# Smart_Smoke_Detector.net
KiCad netlist of a schematic drawn in Altium Designer
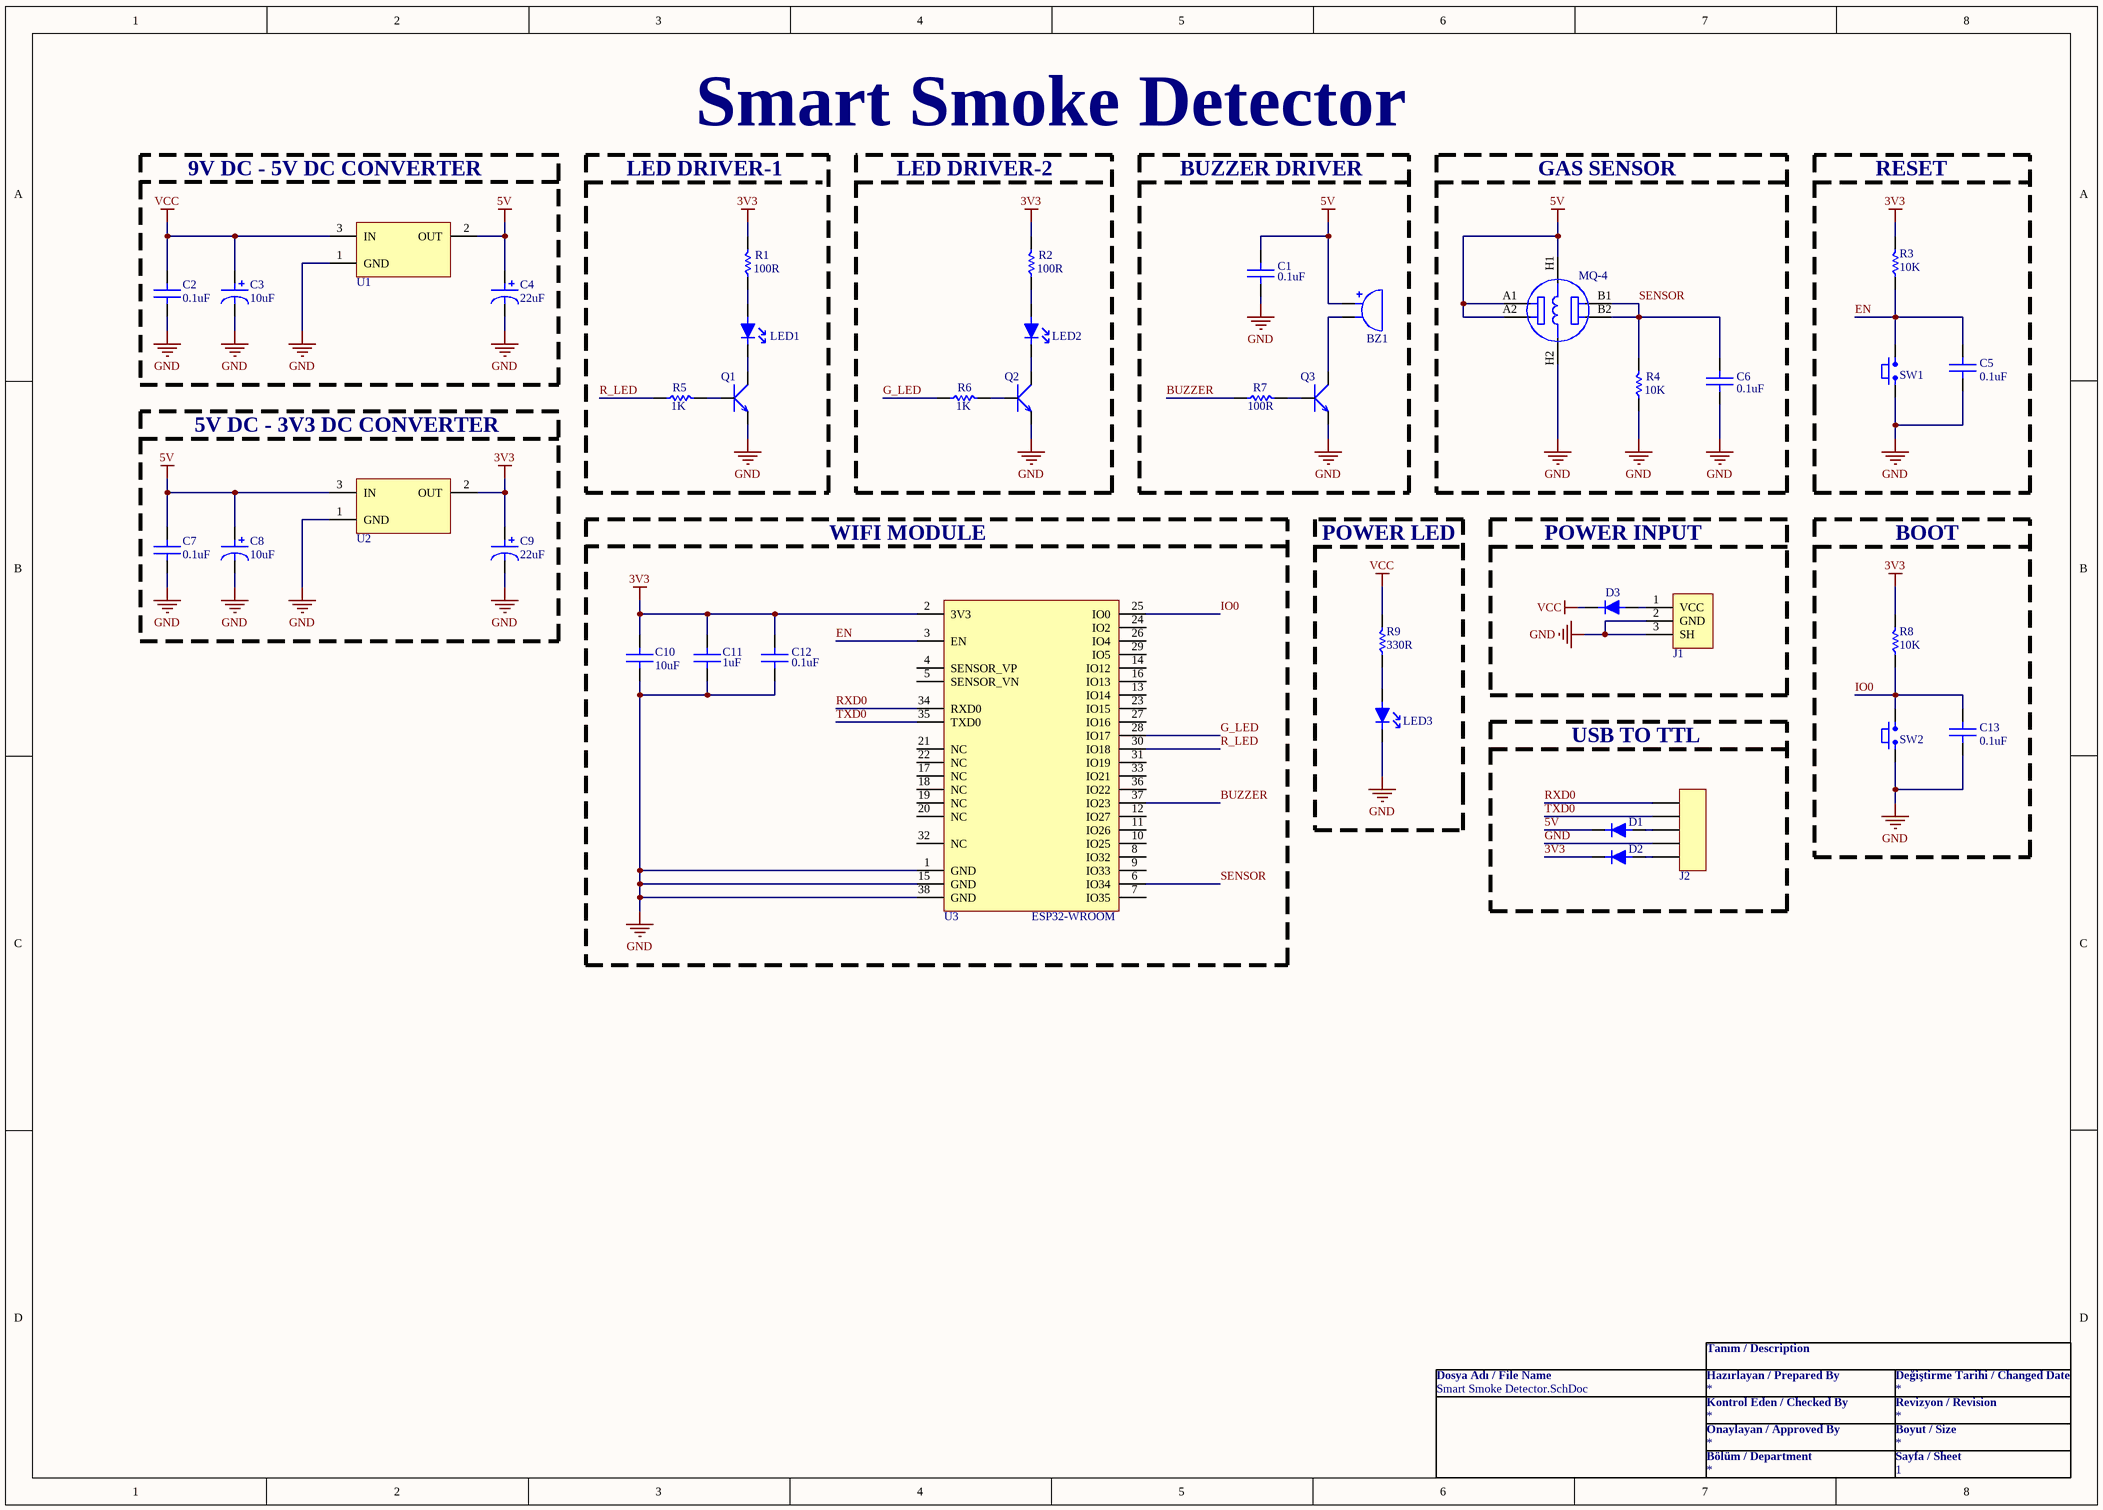
[diagram p0: Smart Smoke Detector.SchDoc]

(export (version "E")
  (design (tool "Eeschema 10.0.6"))
  (components
    (comp (ref "BZ1")
      (value "AI-1223-TWT-3V-2-R")
      (footprint "BUZZER")
      (description "BUZZER MAGNETIC 3V 12MM TH")
      (libsource (lib "Smart Smoke Detector") (part "BUZZER TH"))
    )
    (comp (ref "C1")
      (value "0.1uF")
      (footprint "CAP 0805")
      (description "CAP CER 0.1UF 50V X7R 0805")
      (fields (field (name "Comment") "CC0805KRX7R9BB104"))
      (libsource (lib "Smart Smoke Detector") (part "CAP CER 0.1UF 0805 SMD"))
    )
    (comp (ref "C2")
      (value "0.1uF")
      (footprint "CAP 0805")
      (description "CAP CER 0.1UF 50V X7R 0805")
      (fields (field (name "Comment") "CC0805KRX7R9BB104"))
      (libsource (lib "Smart Smoke Detector") (part "CAP CER 0.1UF 0805 SMD"))
    )
    (comp (ref "C3")
      (value "10uF")
      (footprint "CAP ALUM 10UF")
      (description "CAP ALUM 10UF 20% 16V SMD")
      (fields (field (name "Comment") "875105359001"))
      (libsource (lib "Smart Smoke Detector") (part "CAP ALUM 10UF SMD"))
    )
    (comp (ref "C4")
      (value "22uF")
      (footprint "CAP ALUM 22UF")
      (description "CAP ALUM 22UF 20% 20V SMD")
      (fields (field (name "Comment") "A766EB226M1DLAE060"))
      (libsource (lib "Smart Smoke Detector") (part "CAP ALUM 22UF SMD"))
    )
    (comp (ref "C5")
      (value "0.1uF")
      (footprint "CAP 0805")
      (description "CAP CER 0.1UF 50V X7R 0805")
      (fields (field (name "Comment") "CC0805KRX7R9BB104"))
      (libsource (lib "Smart Smoke Detector") (part "CAP CER 0.1UF 0805 SMD"))
    )
    (comp (ref "C6")
      (value "0.1uF")
      (footprint "CAP 0805")
      (description "CAP CER 0.1UF 50V X7R 0805")
      (fields (field (name "Comment") "CC0805KRX7R9BB104"))
      (libsource (lib "Smart Smoke Detector") (part "CAP CER 0.1UF 0805 SMD"))
    )
    (comp (ref "C7")
      (value "0.1uF")
      (footprint "CAP 0805")
      (description "CAP CER 0.1UF 50V X7R 0805")
      (fields (field (name "Comment") "CC0805KRX7R9BB104"))
      (libsource (lib "Smart Smoke Detector") (part "CAP CER 0.1UF 0805 SMD"))
    )
    (comp (ref "C8")
      (value "10uF")
      (footprint "CAP ALUM 10UF")
      (description "CAP ALUM 10UF 20% 16V SMD")
      (fields (field (name "Comment") "875105359001"))
      (libsource (lib "Smart Smoke Detector") (part "CAP ALUM 10UF SMD"))
    )
    (comp (ref "C9")
      (value "22uF")
      (footprint "CAP ALUM 22UF")
      (description "CAP ALUM 22UF 20% 20V SMD")
      (fields (field (name "Comment") "A766EB226M1DLAE060"))
      (libsource (lib "Smart Smoke Detector") (part "CAP ALUM 22UF SMD"))
    )
    (comp (ref "C10")
      (value "10uF")
      (footprint "CAP 0805")
      (description "CAP CER 10UF 25V X5R 0805")
      (fields (field (name "Comment") "CC0805KKX5R8BB106"))
      (libsource (lib "Smart Smoke Detector") (part "CAP CER 10UF 0805 SMD"))
    )
    (comp (ref "C11")
      (value "1uF")
      (footprint "CAP 0805")
      (description "CAP CER 1UF 50V X7R 0805")
      (fields (field (name "Comment") "CC0805KKX7R9BB105"))
      (libsource (lib "Smart Smoke Detector") (part "CAP CER 1UF 0805 SMD"))
    )
    (comp (ref "C12")
      (value "0.1uF")
      (footprint "CAP 0805")
      (description "CAP CER 0.1UF 50V X7R 0805")
      (fields (field (name "Comment") "CC0805KRX7R9BB104"))
      (libsource (lib "Smart Smoke Detector") (part "CAP CER 0.1UF 0805 SMD"))
    )
    (comp (ref "C13")
      (value "0.1uF")
      (footprint "CAP 0805")
      (description "CAP CER 0.1UF 50V X7R 0805")
      (fields (field (name "Comment") "CC0805KRX7R9BB104"))
      (libsource (lib "Smart Smoke Detector") (part "CAP CER 0.1UF 0805 SMD"))
    )
    (comp (ref "D1")
      (value "1N5819W")
      (footprint "SOD-123F")
      (description "DIODE SCHOTTKY 40V 1A SOD-123F")
      (libsource (lib "Smart Smoke Detector") (part "SCHOTTKY DIODE SMD"))
    )
    (comp (ref "D2")
      (value "1N5819W")
      (footprint "SOD-123F")
      (description "DIODE SCHOTTKY 40V 1A SOD-123F")
      (libsource (lib "Smart Smoke Detector") (part "SCHOTTKY DIODE SMD"))
    )
    (comp (ref "D3")
      (value "1N5819W")
      (footprint "SOD-123F")
      (description "DIODE SCHOTTKY 40V 1A SOD-123F")
      (libsource (lib "Smart Smoke Detector") (part "SCHOTTKY DIODE SMD"))
    )
    (comp (ref "GAS1")
      (value "MQ-4")
      (footprint "MQ-4")
      (description "SENSOR METHANE 2.5V-4 V OUTPUT")
      (fields (field (name "Comment") "SEN-09404"))
      (libsource (lib "Smart Smoke Detector") (part "MQ-4 SENSOR"))
    )
    (comp (ref "J1")
      (value "PJ-036BH-SMT-TR")
      (footprint "POWER JACK")
      (description "PWR JACK 2.5X5.5MM SOLDER")
      (libsource (lib "Smart Smoke Detector") (part "POWER JACK SMD"))
    )
    (comp (ref "J2")
      (value "SMH-105-02-L-S")
      (footprint "SMD HEADER")
      (description "FEMALE HEADER 5POS 2.54MM")
      (libsource (lib "Smart Smoke Detector") (part "HEADER 5POS SMD"))
    )
    (comp (ref "LED1")
      (value "151031SS06000")
      (footprint "RED LED")
      (description "LED RED 3MM ROUND T/H")
      (libsource (lib "Smart Smoke Detector") (part "LED RED TH"))
    )
    (comp (ref "LED2")
      (value "151031VS06000")
      (footprint "GREEN LED")
      (description "LED GREEN 3MM ROUND T/H")
      (libsource (lib "Smart Smoke Detector") (part "LED GREEN TH"))
    )
    (comp (ref "LED3")
      (value "151031VS06000")
      (footprint "GREEN LED")
      (description "LED GREEN 3MM ROUND T/H")
      (libsource (lib "Smart Smoke Detector") (part "LED GREEN TH"))
    )
    (comp (ref "Q1")
      (value "MMBT3904-7-F")
      (footprint "SOT-23-3")
      (description "TRANS NPN 40V 0.2A SOT23-3")
      (libsource (lib "Smart Smoke Detector") (part "NPN TRANSISTOR SMD"))
    )
    (comp (ref "Q2")
      (value "MMBT3904-7-F")
      (footprint "SOT-23-3")
      (description "TRANS NPN 40V 0.2A SOT23-3")
      (libsource (lib "Smart Smoke Detector") (part "NPN TRANSISTOR SMD"))
    )
    (comp (ref "Q3")
      (value "MMBT3904-7-F")
      (footprint "SOT-23-3")
      (description "TRANS NPN 40V 0.2A SOT23-3")
      (libsource (lib "Smart Smoke Detector") (part "NPN TRANSISTOR SMD"))
    )
    (comp (ref "R1")
      (value "100R")
      (footprint "RES 0805")
      (description "RES 100 OHM 1% 1/8W 0805")
      (fields (field (name "Comment") "RMCF0805FT100R"))
      (libsource (lib "Smart Smoke Detector") (part "RES 100 OHM 0805 SMD"))
    )
    (comp (ref "R2")
      (value "100R")
      (footprint "RES 0805")
      (description "RES 100 OHM 1% 1/8W 0805")
      (fields (field (name "Comment") "RMCF0805FT100R"))
      (libsource (lib "Smart Smoke Detector") (part "RES 100 OHM 0805 SMD"))
    )
    (comp (ref "R3")
      (value "10K")
      (footprint "RES 0805")
      (description "RES 10K OHM 5% 1/8W 0805")
      (fields (field (name "Comment") "ERJ-6GEYJ103V"))
      (libsource (lib "Smart Smoke Detector") (part "RES 10K OHM 0805 SMD"))
    )
    (comp (ref "R4")
      (value "10K")
      (footprint "RES 0805")
      (description "RES SMD 10K OHM 5% 1/8W 0805")
      (fields (field (name "Comment") "ERJ-6GEYJ103V"))
      (libsource (lib "Smart Smoke Detector") (part "RES 10K OHM 0805 SMD"))
    )
    (comp (ref "R5")
      (value "1K")
      (footprint "RES 0805")
      (description "RES 1K OHM 1% 1/8W 0805")
      (fields (field (name "Comment") "RC0805FR-071KL"))
      (libsource (lib "Smart Smoke Detector") (part "RES 1K OHM 0805 SMD"))
    )
    (comp (ref "R6")
      (value "1K")
      (footprint "RES 0805")
      (description "RES 1K OHM 1% 1/8W 0805")
      (fields (field (name "Comment") "RC0805FR-071KL"))
      (libsource (lib "Smart Smoke Detector") (part "RES 1K OHM 0805 SMD"))
    )
    (comp (ref "R7")
      (value "100R")
      (footprint "RES 0805")
      (description "RES 100 OHM 1% 1/8W 0805")
      (fields (field (name "Comment") "RMCF0805FT100R"))
      (libsource (lib "Smart Smoke Detector") (part "RES 100 OHM 0805 SMD"))
    )
    (comp (ref "R8")
      (value "10K")
      (footprint "RES 0805")
      (description "RES 10K OHM 5% 1/8W 0805")
      (fields (field (name "Comment") "ERJ-6GEYJ103V"))
      (libsource (lib "Smart Smoke Detector") (part "RES 10K OHM 0805 SMD"))
    )
    (comp (ref "R9")
      (value "330R")
      (footprint "RES 0805")
      (description "RES 330 OHM 1% 1/8W 0805")
      (fields (field (name "Comment") "RC0805FR-07330RL"))
      (libsource (lib "Smart Smoke Detector") (part "RES 330 OHM 0805 SMD"))
    )
    (comp (ref "SW1")
      (value "PTS636 SK25F SMTR LFS")
      (footprint "TACTILE SWITCH")
      (description "SWITCH TACTILE 0.05A 12V")
      (libsource (lib "Smart Smoke Detector") (part "TACTILE SWITCH SMD"))
    )
    (comp (ref "SW2")
      (value "PTS636 SK25F SMTR LFS")
      (footprint "TACTILE SWITCH")
      (description "SWITCH TACTILE 0.05A 12V")
      (libsource (lib "Smart Smoke Detector") (part "TACTILE SWITCH SMD"))
    )
    (comp (ref "U1")
      (value "AMS1117-5.0")
      (footprint "SOT-223")
      (description "IC LDO REG 5V 1A SOT223")
      (libsource (lib "Smart Smoke Detector") (part "LDO REG 5V 1A SMD"))
    )
    (comp (ref "U2")
      (value "AMS1117-3.3")
      (footprint "SOT-223")
      (description "IC LDO REG 3.3V 1A SOT223")
      (libsource (lib "Smart Smoke Detector") (part "LDO REG 3V3 1A SMD"))
    )
    (comp (ref "U3")
      (value "ESP32-WROOM")
      (footprint "ESP32")
      (description "RF TXRX MOD BT WIFI TH SMD")
      (fields (field (name "Comment") "ESP32-WROOM-32E-H4"))
      (libsource (lib "Smart Smoke Detector") (part "ESP32-WROOM-32E"))
    )
  )
  (nets
    (net (code "1") (name "/BUZZER") (class "Default")
      (node (ref "R7") (pin "1") (pinfunction "1_1") (pintype "passive"))
      (node (ref "U3") (pin "37") (pinfunction "IO23_37") (pintype "passive"))
    )
    (net (code "2") (name "/EN") (class "Default")
      (node (ref "C5") (pin "2") (pintype "passive"))
      (node (ref "R3") (pin "1") (pinfunction "1_1") (pintype "passive"))
      (node (ref "SW1") (pin "2") (pintype "passive"))
      (node (ref "U3") (pin "3") (pinfunction "EN_3") (pintype "passive"))
    )
    (net (code "3") (name "/G_LED") (class "Default")
      (node (ref "R6") (pin "1") (pinfunction "1_1") (pintype "passive"))
      (node (ref "U3") (pin "28") (pinfunction "IO17_28") (pintype "passive"))
    )
    (net (code "4") (name "/IO0") (class "Default")
      (node (ref "C13") (pin "2") (pintype "passive"))
      (node (ref "R8") (pin "1") (pinfunction "1_1") (pintype "passive"))
      (node (ref "SW2") (pin "2") (pintype "passive"))
      (node (ref "U3") (pin "25") (pinfunction "IO0_25") (pintype "passive"))
    )
    (net (code "5") (name "/RXD0") (class "Default")
      (node (ref "J2") (pin "1") (pintype "passive"))
      (node (ref "U3") (pin "34") (pinfunction "RXD0_34") (pintype "passive"))
    )
    (net (code "6") (name "/R_LED") (class "Default")
      (node (ref "R5") (pin "1") (pinfunction "1_1") (pintype "passive"))
      (node (ref "U3") (pin "30") (pinfunction "IO18_30") (pintype "passive"))
    )
    (net (code "7") (name "/SENSOR") (class "Default")
      (node (ref "C6") (pin "2") (pintype "passive"))
      (node (ref "GAS1") (pin "B1") (pintype "passive"))
      (node (ref "GAS1") (pin "B2") (pintype "passive"))
      (node (ref "R4") (pin "2") (pinfunction "2_2") (pintype "passive"))
      (node (ref "U3") (pin "6") (pinfunction "IO34_6") (pintype "passive"))
    )
    (net (code "8") (name "/TXD0") (class "Default")
      (node (ref "J2") (pin "2") (pintype "passive"))
      (node (ref "U3") (pin "35") (pinfunction "TXD0_35") (pintype "passive"))
    )
    (net (code "9") (name "3V3") (class "Default")
      (node (ref "C10") (pin "2") (pintype "passive"))
      (node (ref "C11") (pin "1") (pintype "passive"))
      (node (ref "C12") (pin "1") (pintype "passive"))
      (node (ref "C9") (pin "1") (pintype "passive"))
      (node (ref "D2") (pin "2") (pintype "passive"))
      (node (ref "R1") (pin "2") (pinfunction "2_2") (pintype "passive"))
      (node (ref "R2") (pin "2") (pinfunction "2_2") (pintype "passive"))
      (node (ref "R3") (pin "2") (pinfunction "2_2") (pintype "passive"))
      (node (ref "R8") (pin "2") (pinfunction "2_2") (pintype "passive"))
      (node (ref "U2") (pin "2") (pinfunction "OUT_2") (pintype "passive"))
      (node (ref "U3") (pin "2") (pinfunction "3V3_2") (pintype "passive"))
    )
    (net (code "10") (name "5V") (class "Default")
      (node (ref "BZ1") (pin "1") (pintype "passive"))
      (node (ref "C1") (pin "2") (pintype "passive"))
      (node (ref "C4") (pin "1") (pintype "passive"))
      (node (ref "C7") (pin "2") (pintype "passive"))
      (node (ref "C8") (pin "1") (pintype "passive"))
      (node (ref "D1") (pin "2") (pintype "passive"))
      (node (ref "GAS1") (pin "A1") (pintype "passive"))
      (node (ref "GAS1") (pin "A2") (pintype "passive"))
      (node (ref "GAS1") (pin "H1") (pintype "passive"))
      (node (ref "U1") (pin "2") (pinfunction "OUT_2") (pintype "passive"))
      (node (ref "U2") (pin "3") (pinfunction "IN_3") (pintype "passive"))
    )
    (net (code "11") (name "GND") (class "Default")
      (node (ref "C1") (pin "1") (pintype "passive"))
      (node (ref "C10") (pin "1") (pintype "passive"))
      (node (ref "C11") (pin "2") (pintype "passive"))
      (node (ref "C12") (pin "2") (pintype "passive"))
      (node (ref "C13") (pin "1") (pintype "passive"))
      (node (ref "C2") (pin "1") (pintype "passive"))
      (node (ref "C3") (pin "2") (pintype "passive"))
      (node (ref "C4") (pin "2") (pintype "passive"))
      (node (ref "C5") (pin "1") (pintype "passive"))
      (node (ref "C6") (pin "1") (pintype "passive"))
      (node (ref "C7") (pin "1") (pintype "passive"))
      (node (ref "C8") (pin "2") (pintype "passive"))
      (node (ref "C9") (pin "2") (pintype "passive"))
      (node (ref "GAS1") (pin "H2") (pintype "passive"))
      (node (ref "J1") (pin "2") (pinfunction "GND_2") (pintype "passive"))
      (node (ref "J1") (pin "3") (pinfunction "SH_3") (pintype "passive"))
      (node (ref "J2") (pin "4") (pintype "passive"))
      (node (ref "LED3") (pin "2") (pintype "passive"))
      (node (ref "Q1") (pin "2") (pintype "passive"))
      (node (ref "Q2") (pin "2") (pintype "passive"))
      (node (ref "Q3") (pin "2") (pintype "passive"))
      (node (ref "R4") (pin "1") (pinfunction "1_1") (pintype "passive"))
      (node (ref "SW1") (pin "1") (pintype "passive"))
      (node (ref "SW2") (pin "1") (pintype "passive"))
      (node (ref "U1") (pin "1") (pinfunction "GND_1") (pintype "passive"))
      (node (ref "U2") (pin "1") (pinfunction "GND_1") (pintype "passive"))
      (node (ref "U3") (pin "1") (pinfunction "GND_1") (pintype "passive"))
      (node (ref "U3") (pin "15") (pinfunction "GND_15") (pintype "passive"))
      (node (ref "U3") (pin "38") (pinfunction "GND_38") (pintype "passive"))
    )
    (net (code "12") (name "Net-(BZ1-Pad2)") (class "Default")
      (node (ref "BZ1") (pin "2") (pintype "passive"))
      (node (ref "Q3") (pin "3") (pintype "passive"))
    )
    (net (code "13") (name "Net-(D1-Pad1)") (class "Default")
      (node (ref "D1") (pin "1") (pintype "passive"))
      (node (ref "J2") (pin "3") (pintype "passive"))
    )
    (net (code "14") (name "Net-(D2-Pad1)") (class "Default")
      (node (ref "D2") (pin "1") (pintype "passive"))
      (node (ref "J2") (pin "5") (pintype "passive"))
    )
    (net (code "15") (name "Net-(J1-VCC)") (class "Default")
      (node (ref "D3") (pin "1") (pintype "passive"))
      (node (ref "J1") (pin "1") (pinfunction "VCC_1") (pintype "passive"))
    )
    (net (code "16") (name "Net-(LED1-Pad1)") (class "Default")
      (node (ref "LED1") (pin "1") (pintype "passive"))
      (node (ref "R1") (pin "1") (pinfunction "1_1") (pintype "passive"))
    )
    (net (code "17") (name "Net-(LED1-Pad2)") (class "Default")
      (node (ref "LED1") (pin "2") (pintype "passive"))
      (node (ref "Q1") (pin "3") (pintype "passive"))
    )
    (net (code "18") (name "Net-(LED2-Pad1)") (class "Default")
      (node (ref "LED2") (pin "1") (pintype "passive"))
      (node (ref "R2") (pin "1") (pinfunction "1_1") (pintype "passive"))
    )
    (net (code "19") (name "Net-(LED2-Pad2)") (class "Default")
      (node (ref "LED2") (pin "2") (pintype "passive"))
      (node (ref "Q2") (pin "3") (pintype "passive"))
    )
    (net (code "20") (name "Net-(LED3-Pad1)") (class "Default")
      (node (ref "LED3") (pin "1") (pintype "passive"))
      (node (ref "R9") (pin "1") (pinfunction "1_1") (pintype "passive"))
    )
    (net (code "21") (name "Net-(Q1-Pad1)") (class "Default")
      (node (ref "Q1") (pin "1") (pintype "passive"))
      (node (ref "R5") (pin "2") (pinfunction "2_2") (pintype "passive"))
    )
    (net (code "22") (name "Net-(Q2-Pad1)") (class "Default")
      (node (ref "Q2") (pin "1") (pintype "passive"))
      (node (ref "R6") (pin "2") (pinfunction "2_2") (pintype "passive"))
    )
    (net (code "23") (name "Net-(Q3-Pad1)") (class "Default")
      (node (ref "Q3") (pin "1") (pintype "passive"))
      (node (ref "R7") (pin "2") (pinfunction "2_2") (pintype "passive"))
    )
    (net (code "24") (name "VCC") (class "Default")
      (node (ref "C2") (pin "2") (pintype "passive"))
      (node (ref "C3") (pin "1") (pintype "passive"))
      (node (ref "D3") (pin "2") (pintype "passive"))
      (node (ref "R9") (pin "2") (pinfunction "2_2") (pintype "passive"))
      (node (ref "U1") (pin "3") (pinfunction "IN_3") (pintype "passive"))
    )
    (net (code "25") (name "unconnected-(U3-IO2-Pad24)") (class "Default")
      (node (ref "U3") (pin "24") (pinfunction "IO2_24") (pintype "passive"))
    )
    (net (code "26") (name "unconnected-(U3-IO4-Pad26)") (class "Default")
      (node (ref "U3") (pin "26") (pinfunction "IO4_26") (pintype "passive"))
    )
    (net (code "27") (name "unconnected-(U3-IO5-Pad29)") (class "Default")
      (node (ref "U3") (pin "29") (pinfunction "IO5_29") (pintype "passive"))
    )
    (net (code "28") (name "unconnected-(U3-IO12-Pad14)") (class "Default")
      (node (ref "U3") (pin "14") (pinfunction "IO12_14") (pintype "passive"))
    )
    (net (code "29") (name "unconnected-(U3-IO13-Pad16)") (class "Default")
      (node (ref "U3") (pin "16") (pinfunction "IO13_16") (pintype "passive"))
    )
    (net (code "30") (name "unconnected-(U3-IO14-Pad13)") (class "Default")
      (node (ref "U3") (pin "13") (pinfunction "IO14_13") (pintype "passive"))
    )
    (net (code "31") (name "unconnected-(U3-IO15-Pad23)") (class "Default")
      (node (ref "U3") (pin "23") (pinfunction "IO15_23") (pintype "passive"))
    )
    (net (code "32") (name "unconnected-(U3-IO16-Pad27)") (class "Default")
      (node (ref "U3") (pin "27") (pinfunction "IO16_27") (pintype "passive"))
    )
    (net (code "33") (name "unconnected-(U3-IO19-Pad31)") (class "Default")
      (node (ref "U3") (pin "31") (pinfunction "IO19_31") (pintype "passive"))
    )
    (net (code "34") (name "unconnected-(U3-IO21-Pad33)") (class "Default")
      (node (ref "U3") (pin "33") (pinfunction "IO21_33") (pintype "passive"))
    )
    (net (code "35") (name "unconnected-(U3-IO22-Pad36)") (class "Default")
      (node (ref "U3") (pin "36") (pinfunction "IO22_36") (pintype "passive"))
    )
    (net (code "36") (name "unconnected-(U3-IO25-Pad10)") (class "Default")
      (node (ref "U3") (pin "10") (pinfunction "IO25_10") (pintype "passive"))
    )
    (net (code "37") (name "unconnected-(U3-IO26-Pad11)") (class "Default")
      (node (ref "U3") (pin "11") (pinfunction "IO26_11") (pintype "passive"))
    )
    (net (code "38") (name "unconnected-(U3-IO27-Pad12)") (class "Default")
      (node (ref "U3") (pin "12") (pinfunction "IO27_12") (pintype "passive"))
    )
    (net (code "39") (name "unconnected-(U3-IO32-Pad8)") (class "Default")
      (node (ref "U3") (pin "8") (pinfunction "IO32_8") (pintype "passive"))
    )
    (net (code "40") (name "unconnected-(U3-IO33-Pad9)") (class "Default")
      (node (ref "U3") (pin "9") (pinfunction "IO33_9") (pintype "passive"))
    )
    (net (code "41") (name "unconnected-(U3-IO35-Pad7)") (class "Default")
      (node (ref "U3") (pin "7") (pinfunction "IO35_7") (pintype "passive"))
    )
    (net (code "42") (name "unconnected-(U3-NC-Pad17)") (class "Default")
      (node (ref "U3") (pin "17") (pinfunction "NC_17") (pintype "passive"))
    )
    (net (code "43") (name "unconnected-(U3-NC-Pad18)") (class "Default")
      (node (ref "U3") (pin "18") (pinfunction "NC_18") (pintype "passive"))
    )
    (net (code "44") (name "unconnected-(U3-NC-Pad19)") (class "Default")
      (node (ref "U3") (pin "19") (pinfunction "NC_19") (pintype "passive"))
    )
    (net (code "45") (name "unconnected-(U3-NC-Pad20)") (class "Default")
      (node (ref "U3") (pin "20") (pinfunction "NC_20") (pintype "passive"))
    )
    (net (code "46") (name "unconnected-(U3-NC-Pad21)") (class "Default")
      (node (ref "U3") (pin "21") (pinfunction "NC_21") (pintype "passive"))
    )
    (net (code "47") (name "unconnected-(U3-NC-Pad22)") (class "Default")
      (node (ref "U3") (pin "22") (pinfunction "NC_22") (pintype "passive"))
    )
    (net (code "48") (name "unconnected-(U3-NC-Pad32)") (class "Default")
      (node (ref "U3") (pin "32") (pinfunction "NC_32") (pintype "passive"))
    )
    (net (code "49") (name "unconnected-(U3-SENSOR_VN-Pad5)") (class "Default")
      (node (ref "U3") (pin "5") (pinfunction "SENSOR_VN_5") (pintype "passive"))
    )
    (net (code "50") (name "unconnected-(U3-SENSOR_VP-Pad4)") (class "Default")
      (node (ref "U3") (pin "4") (pinfunction "SENSOR_VP_4") (pintype "passive"))
    )
  )
)
